# OMSI_TABLE_R12_v1.net
KiCad netlist of a schematic drawn in EAGLE
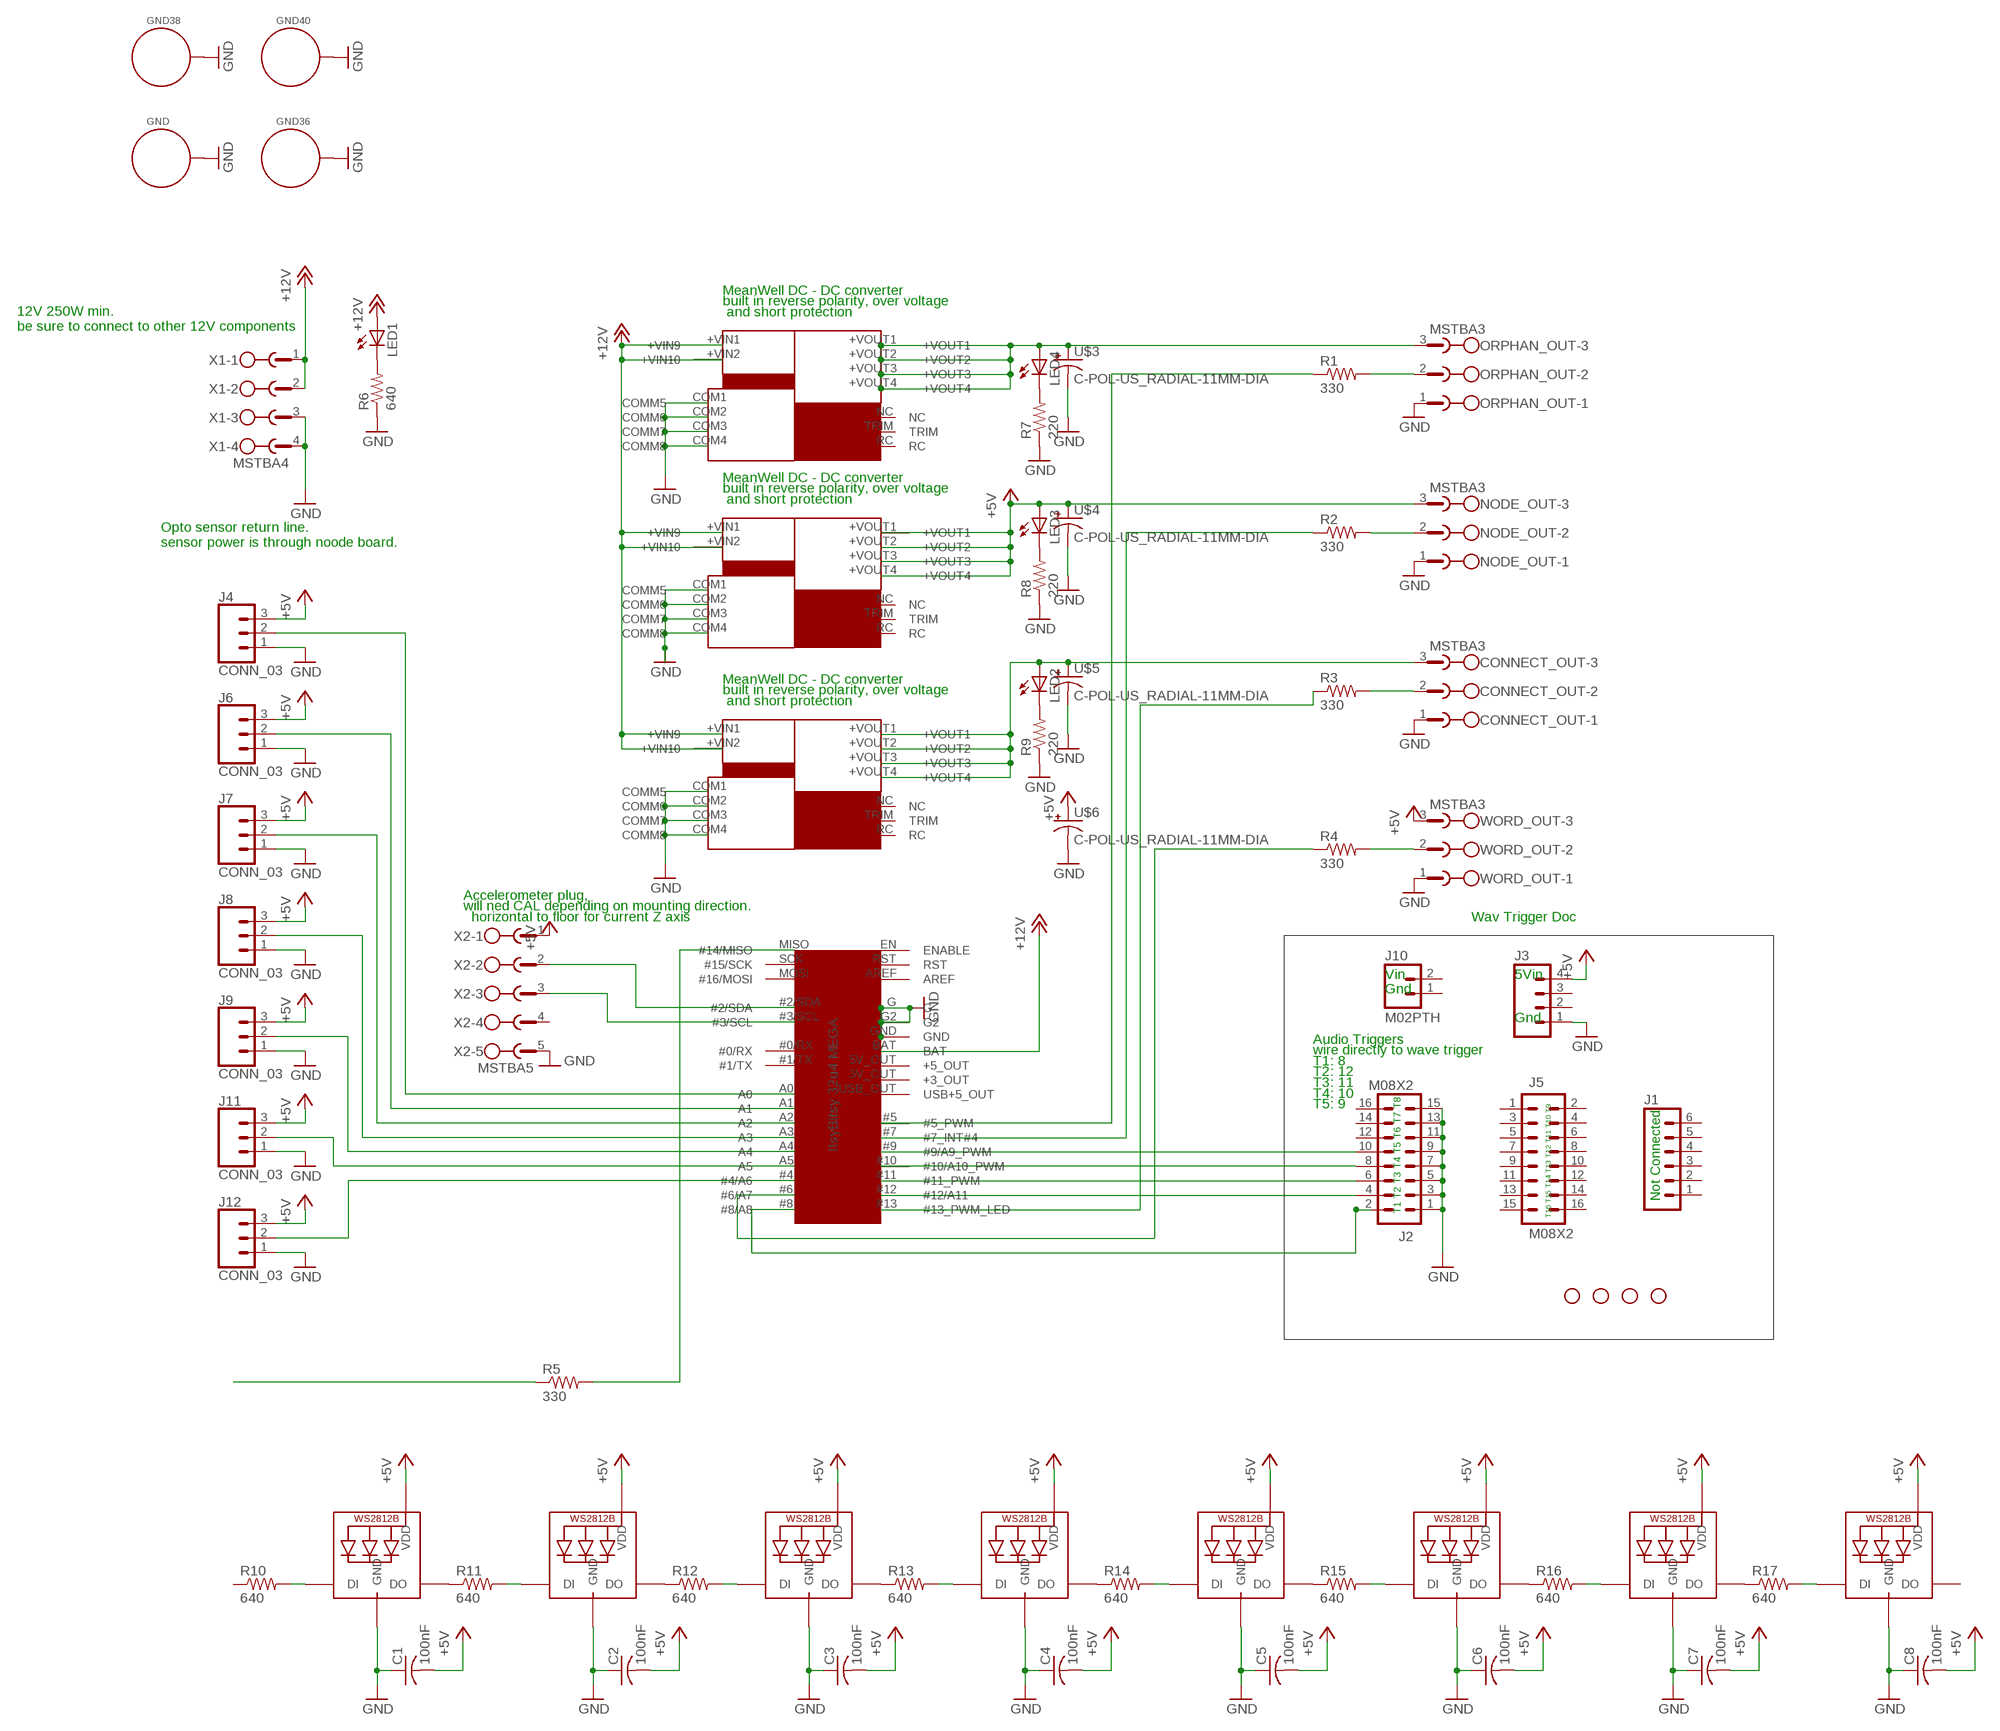
[diagram p0: schematic, sheet 1]

(export (version "E")
  (design (tool "Eeschema 10.0.6"))
  (components
    (comp (ref "C1")
      (value "100nF")
      (footprint "eagle-import:C0805")
      (libsource (lib "eagle-import") (part "C-USC0805"))
    )
    (comp (ref "C2")
      (value "100nF")
      (footprint "eagle-import:C0805")
      (libsource (lib "eagle-import") (part "C-USC0805"))
    )
    (comp (ref "C3")
      (value "100nF")
      (footprint "eagle-import:C0805")
      (libsource (lib "eagle-import") (part "C-USC0805"))
    )
    (comp (ref "C4")
      (value "100nF")
      (footprint "eagle-import:C0805")
      (libsource (lib "eagle-import") (part "C-USC0805"))
    )
    (comp (ref "C5")
      (value "100nF")
      (footprint "eagle-import:C0805")
      (libsource (lib "eagle-import") (part "C-USC0805"))
    )
    (comp (ref "C6")
      (value "100nF")
      (footprint "eagle-import:C0805")
      (libsource (lib "eagle-import") (part "C-USC0805"))
    )
    (comp (ref "C7")
      (value "100nF")
      (footprint "eagle-import:C0805")
      (libsource (lib "eagle-import") (part "C-USC0805"))
    )
    (comp (ref "C8")
      (value "100nF")
      (footprint "eagle-import:C0805")
      (libsource (lib "eagle-import") (part "C-USC0805"))
    )
    (comp (ref "CONNECT_OUT")
      (value "MSTBA3")
      (footprint "eagle-import:MSTBA3")
      (fields (field (name "MF") "FARNELL") (field (name "MPN") "1757255"))
      (libsource (lib "eagle-import") (part "MSTBA3"))
    )
    (comp (ref "GND")
      (value "STANDOFF_ELECTRICAL5-32")
      (footprint "eagle-import:STANDOFF_ELECTRICAL_5_32")
      (libsource (lib "eagle-import") (part "STANDOFF_ELECTRICAL5-32"))
    )
    (comp (ref "GND36")
      (value "STANDOFF_ELECTRICAL5-32")
      (footprint "eagle-import:STANDOFF_ELECTRICAL_5_32")
      (libsource (lib "eagle-import") (part "STANDOFF_ELECTRICAL5-32"))
    )
    (comp (ref "GND38")
      (value "STANDOFF_ELECTRICAL5-32")
      (footprint "eagle-import:STANDOFF_ELECTRICAL_5_32")
      (libsource (lib "eagle-import") (part "STANDOFF_ELECTRICAL5-32"))
    )
    (comp (ref "GND40")
      (value "STANDOFF_ELECTRICAL5-32")
      (footprint "eagle-import:STANDOFF_ELECTRICAL_5_32")
      (libsource (lib "eagle-import") (part "STANDOFF_ELECTRICAL5-32"))
    )
    (comp (ref "J1")
      (value "M06SIP")
      (footprint "eagle-import:1X06")
      (libsource (lib "eagle-import") (part "M06SIP"))
    )
    (comp (ref "J2")
      (value "M08X2")
      (footprint "eagle-import:2X8")
      (libsource (lib "eagle-import") (part "M08X2"))
    )
    (comp (ref "J3")
      (value "M04PTH")
      (footprint "eagle-import:1X04")
      (libsource (lib "eagle-import") (part "M04PTH"))
    )
    (comp (ref "J4")
      (value "CONN_03")
      (footprint "eagle-import:1X03_3.5MM_RA")
      (libsource (lib "eagle-import") (part "CONN_03"))
    )
    (comp (ref "J5")
      (value "M08X2")
      (footprint "eagle-import:2X8")
      (libsource (lib "eagle-import") (part "M08X2"))
    )
    (comp (ref "J6")
      (value "CONN_03")
      (footprint "eagle-import:1X03_3.5MM_RA")
      (libsource (lib "eagle-import") (part "CONN_03"))
    )
    (comp (ref "J7")
      (value "CONN_03")
      (footprint "eagle-import:1X03_3.5MM_RA")
      (libsource (lib "eagle-import") (part "CONN_03"))
    )
    (comp (ref "J8")
      (value "CONN_03")
      (footprint "eagle-import:1X03_3.5MM_RA")
      (libsource (lib "eagle-import") (part "CONN_03"))
    )
    (comp (ref "J9")
      (value "CONN_03")
      (footprint "eagle-import:1X03_3.5MM_RA")
      (libsource (lib "eagle-import") (part "CONN_03"))
    )
    (comp (ref "J10")
      (value "M02PTH")
      (footprint "eagle-import:1X02")
      (libsource (lib "eagle-import") (part "M02PTH"))
    )
    (comp (ref "J11")
      (value "CONN_03")
      (footprint "eagle-import:1X03_3.5MM_RA")
      (libsource (lib "eagle-import") (part "CONN_03"))
    )
    (comp (ref "J12")
      (value "CONN_03")
      (footprint "eagle-import:1X03_3.5MM_RA")
      (libsource (lib "eagle-import") (part "CONN_03"))
    )
    (comp (ref "LED1")
      (value "LEDCHIPLED_1206")
      (footprint "eagle-import:CHIPLED_1206")
      (libsource (lib "eagle-import") (part "LEDCHIPLED_1206"))
    )
    (comp (ref "LED2")
      (value "LEDCHIPLED_1206")
      (footprint "eagle-import:CHIPLED_1206")
      (libsource (lib "eagle-import") (part "LEDCHIPLED_1206"))
    )
    (comp (ref "LED3")
      (value "LEDCHIPLED_1206")
      (footprint "eagle-import:CHIPLED_1206")
      (libsource (lib "eagle-import") (part "LEDCHIPLED_1206"))
    )
    (comp (ref "LED4")
      (value "LEDCHIPLED_1206")
      (footprint "eagle-import:CHIPLED_1206")
      (libsource (lib "eagle-import") (part "LEDCHIPLED_1206"))
    )
    (comp (ref "LED5")
      (value "WS2812B")
      (footprint "eagle-import:WS2812D-F5")
      (libsource (lib "eagle-import") (part "WS2812B"))
    )
    (comp (ref "LED6")
      (value "WS2812B")
      (footprint "eagle-import:WS2812D-F5")
      (libsource (lib "eagle-import") (part "WS2812B"))
    )
    (comp (ref "LED7")
      (value "WS2812B")
      (footprint "eagle-import:WS2812D-F5")
      (libsource (lib "eagle-import") (part "WS2812B"))
    )
    (comp (ref "LED8")
      (value "WS2812B")
      (footprint "eagle-import:WS2812D-F5")
      (libsource (lib "eagle-import") (part "WS2812B"))
    )
    (comp (ref "LED9")
      (value "WS2812B")
      (footprint "eagle-import:WS2812D-F5")
      (libsource (lib "eagle-import") (part "WS2812B"))
    )
    (comp (ref "LED10")
      (value "WS2812B")
      (footprint "eagle-import:WS2812D-F5")
      (libsource (lib "eagle-import") (part "WS2812B"))
    )
    (comp (ref "LED11")
      (value "WS2812B")
      (footprint "eagle-import:WS2812D-F5")
      (libsource (lib "eagle-import") (part "WS2812B"))
    )
    (comp (ref "LED12")
      (value "WS2812B")
      (footprint "eagle-import:WS2812D-F5")
      (libsource (lib "eagle-import") (part "WS2812B"))
    )
    (comp (ref "MEANWELL_NID100_1")
      (value "MEANWELL_NID100")
      (footprint "eagle-import:MEANWELL_NID100")
      (libsource (lib "eagle-import") (part "MEANWELL_NID100"))
    )
    (comp (ref "MEANWELL_NID100_2")
      (value "MEANWELL_NID100")
      (footprint "eagle-import:MEANWELL_NID100")
      (libsource (lib "eagle-import") (part "MEANWELL_NID100"))
    )
    (comp (ref "MEANWELL_NID100_3")
      (value "MEANWELL_NID100")
      (footprint "eagle-import:MEANWELL_NID100")
      (libsource (lib "eagle-import") (part "MEANWELL_NID100"))
    )
    (comp (ref "NODE_OUT")
      (value "MSTBA3")
      (footprint "eagle-import:MSTBA3")
      (fields (field (name "MF") "FARNELL") (field (name "MPN") "1757255"))
      (libsource (lib "eagle-import") (part "MSTBA3"))
    )
    (comp (ref "ORPHAN_OUT")
      (value "MSTBA3")
      (footprint "eagle-import:MSTBA3")
      (fields (field (name "MF") "FARNELL") (field (name "MPN") "1757255"))
      (libsource (lib "eagle-import") (part "MSTBA3"))
    )
    (comp (ref "R1")
      (value "330")
      (footprint "eagle-import:RESAD1176W63L850D250B")
      (libsource (lib "eagle-import") (part "R-USAXIAL-11.7MM-PITCH_"))
    )
    (comp (ref "R2")
      (value "330")
      (footprint "eagle-import:RESAD1176W63L850D250B")
      (libsource (lib "eagle-import") (part "R-USAXIAL-11.7MM-PITCH_"))
    )
    (comp (ref "R3")
      (value "330")
      (footprint "eagle-import:RESAD1176W63L850D250B")
      (libsource (lib "eagle-import") (part "R-USAXIAL-11.7MM-PITCH_"))
    )
    (comp (ref "R4")
      (value "330")
      (footprint "eagle-import:RESAD1176W63L850D250B")
      (libsource (lib "eagle-import") (part "R-USAXIAL-11.7MM-PITCH_"))
    )
    (comp (ref "R5")
      (value "330")
      (footprint "eagle-import:RESAD1176W63L850D250B")
      (libsource (lib "eagle-import") (part "R-USAXIAL-11.7MM-PITCH_"))
    )
    (comp (ref "R6")
      (value "640")
      (footprint "eagle-import:R0805")
      (libsource (lib "eagle-import") (part "adafruit_420_R-US_R0805"))
    )
    (comp (ref "R7")
      (value "220")
      (footprint "eagle-import:R0805")
      (libsource (lib "eagle-import") (part "R-US_R0805"))
    )
    (comp (ref "R8")
      (value "220")
      (footprint "eagle-import:R0805")
      (libsource (lib "eagle-import") (part "R-US_R0805"))
    )
    (comp (ref "R9")
      (value "220")
      (footprint "eagle-import:R0805")
      (libsource (lib "eagle-import") (part "R-US_R0805"))
    )
    (comp (ref "R10")
      (value "640")
      (footprint "eagle-import:R0805")
      (libsource (lib "eagle-import") (part "adafruit_420_R-US_R0805"))
    )
    (comp (ref "R11")
      (value "640")
      (footprint "eagle-import:R0805")
      (libsource (lib "eagle-import") (part "adafruit_420_R-US_R0805"))
    )
    (comp (ref "R12")
      (value "640")
      (footprint "eagle-import:R0805")
      (libsource (lib "eagle-import") (part "adafruit_420_R-US_R0805"))
    )
    (comp (ref "R13")
      (value "640")
      (footprint "eagle-import:R0805")
      (libsource (lib "eagle-import") (part "adafruit_420_R-US_R0805"))
    )
    (comp (ref "R14")
      (value "640")
      (footprint "eagle-import:R0805")
      (libsource (lib "eagle-import") (part "adafruit_420_R-US_R0805"))
    )
    (comp (ref "R15")
      (value "640")
      (footprint "eagle-import:R0805")
      (libsource (lib "eagle-import") (part "adafruit_420_R-US_R0805"))
    )
    (comp (ref "R16")
      (value "640")
      (footprint "eagle-import:R0805")
      (libsource (lib "eagle-import") (part "adafruit_420_R-US_R0805"))
    )
    (comp (ref "R17")
      (value "640")
      (footprint "eagle-import:R0805")
      (libsource (lib "eagle-import") (part "adafruit_420_R-US_R0805"))
    )
    (comp (ref "STANDOFF5")
      (value "STAND-OFF")
      (footprint "eagle-import:STAND-OFF")
      (libsource (lib "eagle-import") (part "STAND-OFF"))
    )
    (comp (ref "STANDOFF6")
      (value "STAND-OFF")
      (footprint "eagle-import:STAND-OFF")
      (libsource (lib "eagle-import") (part "STAND-OFF"))
    )
    (comp (ref "STANDOFF7")
      (value "STAND-OFF")
      (footprint "eagle-import:STAND-OFF")
      (libsource (lib "eagle-import") (part "STAND-OFF"))
    )
    (comp (ref "STANDOFF8")
      (value "STAND-OFF")
      (footprint "eagle-import:STAND-OFF")
      (libsource (lib "eagle-import") (part "STAND-OFF"))
    )
    (comp (ref "U$1")
      (value "ITSYBITSY_32U4")
      (footprint "eagle-import:ITSYBITSY_32U4")
      (libsource (lib "eagle-import") (part "ITSYBITSY_32U4"))
    )
    (comp (ref "U$3")
      (value "C-POL-US_RADIAL-11MM-DIA")
      (footprint "eagle-import:CAPPRD508W65D1000H1100B")
      (libsource (lib "eagle-import") (part "C-POL-USRADIAL-11MM-DIA_"))
    )
    (comp (ref "U$4")
      (value "C-POL-US_RADIAL-11MM-DIA")
      (footprint "eagle-import:CAPPRD508W65D1000H1100B")
      (libsource (lib "eagle-import") (part "C-POL-USRADIAL-11MM-DIA_"))
    )
    (comp (ref "U$5")
      (value "C-POL-US_RADIAL-11MM-DIA")
      (footprint "eagle-import:CAPPRD508W65D1000H1100B")
      (libsource (lib "eagle-import") (part "C-POL-USRADIAL-11MM-DIA_"))
    )
    (comp (ref "U$6")
      (value "C-POL-US_RADIAL-11MM-DIA")
      (footprint "eagle-import:CAPPRD508W65D1000H1100B")
      (libsource (lib "eagle-import") (part "C-POL-USRADIAL-11MM-DIA_"))
    )
    (comp (ref "WORD_OUT")
      (value "MSTBA3")
      (footprint "eagle-import:MSTBA3")
      (fields (field (name "MF") "FARNELL") (field (name "MPN") "1757255"))
      (libsource (lib "eagle-import") (part "MSTBA3"))
    )
    (comp (ref "X1")
      (value "MSTBA4")
      (footprint "eagle-import:MSTBA4")
      (fields (field (name "MF") "FARNELL") (field (name "MPN") "1757268"))
      (libsource (lib "eagle-import") (part "MSTBA4"))
    )
    (comp (ref "X2")
      (value "MSTBA5")
      (footprint "eagle-import:MSTBA5")
      (fields (field (name "MPN") "1757271"))
      (libsource (lib "eagle-import") (part "MSTBA5"))
    )
  )
  (nets
    (net (code "1") (name "+5V") (class "Default")
      (node (ref "C1") (pin "2") (pinfunction "2_2") (pintype "passive"))
      (node (ref "C2") (pin "2") (pinfunction "2_2") (pintype "passive"))
      (node (ref "C3") (pin "2") (pinfunction "2_2") (pintype "passive"))
      (node (ref "C4") (pin "2") (pinfunction "2_2") (pintype "passive"))
      (node (ref "C5") (pin "2") (pinfunction "2_2") (pintype "passive"))
      (node (ref "C6") (pin "2") (pinfunction "2_2") (pintype "passive"))
      (node (ref "C7") (pin "2") (pinfunction "2_2") (pintype "passive"))
      (node (ref "C8") (pin "2") (pinfunction "2_2") (pintype "passive"))
      (node (ref "J11") (pin "3") (pinfunction "3_3") (pintype "passive"))
      (node (ref "J12") (pin "3") (pinfunction "3_3") (pintype "passive"))
      (node (ref "J3") (pin "4") (pinfunction "4_4") (pintype "passive"))
      (node (ref "J4") (pin "3") (pinfunction "3_3") (pintype "passive"))
      (node (ref "J6") (pin "3") (pinfunction "3_3") (pintype "passive"))
      (node (ref "J7") (pin "3") (pinfunction "3_3") (pintype "passive"))
      (node (ref "J8") (pin "3") (pinfunction "3_3") (pintype "passive"))
      (node (ref "J9") (pin "3") (pinfunction "3_3") (pintype "passive"))
      (node (ref "LED10") (pin "P$2") (pinfunction "VDD_P$2") (pintype "power_in"))
      (node (ref "LED11") (pin "P$2") (pinfunction "VDD_P$2") (pintype "power_in"))
      (node (ref "LED12") (pin "P$2") (pinfunction "VDD_P$2") (pintype "power_in"))
      (node (ref "LED3") (pin "A") (pinfunction "A_A") (pintype "passive"))
      (node (ref "LED5") (pin "P$2") (pinfunction "VDD_P$2") (pintype "power_in"))
      (node (ref "LED6") (pin "P$2") (pinfunction "VDD_P$2") (pintype "power_in"))
      (node (ref "LED7") (pin "P$2") (pinfunction "VDD_P$2") (pintype "power_in"))
      (node (ref "LED8") (pin "P$2") (pinfunction "VDD_P$2") (pintype "power_in"))
      (node (ref "LED9") (pin "P$2") (pinfunction "VDD_P$2") (pintype "power_in"))
      (node (ref "MEANWELL_NID100_3") (pin "+VOUT1") (pinfunction "+VOUT1_+VOUT1") (pintype "power_in"))
      (node (ref "MEANWELL_NID100_3") (pin "+VOUT2") (pinfunction "+VOUT2_+VOUT2") (pintype "power_in"))
      (node (ref "MEANWELL_NID100_3") (pin "+VOUT3") (pinfunction "+VOUT3_+VOUT3") (pintype "power_in"))
      (node (ref "MEANWELL_NID100_3") (pin "+VOUT4") (pinfunction "+VOUT4_+VOUT4") (pintype "power_in"))
      (node (ref "NODE_OUT") (pin "3") (pinfunction "1_3") (pintype "passive"))
      (node (ref "U$4") (pin "1") (pinfunction "+_1") (pintype "passive"))
      (node (ref "U$6") (pin "1") (pinfunction "+_1") (pintype "passive"))
      (node (ref "WORD_OUT") (pin "3") (pinfunction "1_3") (pintype "passive"))
      (node (ref "X2") (pin "1") (pinfunction "1_1") (pintype "passive"))
    )
    (net (code "2") (name "+12V") (class "Default")
      (node (ref "LED1") (pin "A") (pinfunction "A_A") (pintype "passive"))
      (node (ref "MEANWELL_NID100_1") (pin "+VIN1") (pinfunction "+VIN9_+VIN1") (pintype "power_in"))
      (node (ref "MEANWELL_NID100_1") (pin "+VIN2") (pinfunction "+VIN10_+VIN2") (pintype "power_in"))
      (node (ref "MEANWELL_NID100_2") (pin "+VIN1") (pinfunction "+VIN9_+VIN1") (pintype "power_in"))
      (node (ref "MEANWELL_NID100_2") (pin "+VIN2") (pinfunction "+VIN10_+VIN2") (pintype "power_in"))
      (node (ref "MEANWELL_NID100_3") (pin "+VIN1") (pinfunction "+VIN9_+VIN1") (pintype "power_in"))
      (node (ref "MEANWELL_NID100_3") (pin "+VIN2") (pinfunction "+VIN10_+VIN2") (pintype "power_in"))
      (node (ref "U$1") (pin "BAT") (pinfunction "BAT_BAT") (pintype "power_in"))
      (node (ref "X1") (pin "1") (pinfunction "1_1") (pintype "passive"))
      (node (ref "X1") (pin "2") (pinfunction "1_2") (pintype "passive"))
    )
    (net (code "3") (name "/+3_OUT") (class "Default")
      (node (ref "U$1") (pin "3V_OUT") (pinfunction "+3_OUT_3V_OUT") (pintype "power_in"))
    )
    (net (code "4") (name "/+5_OUT") (class "Default")
      (node (ref "U$1") (pin "5V_OUT") (pinfunction "+5_OUT_5V_OUT") (pintype "power_in"))
    )
    (net (code "5") (name "/AREF") (class "Default")
      (node (ref "U$1") (pin "AREF") (pinfunction "AREF_AREF") (pintype "power_in"))
    )
    (net (code "6") (name "/RST") (class "Default")
      (node (ref "U$1") (pin "RST") (pinfunction "RST_RST") (pintype "power_in"))
    )
    (net (code "7") (name "/USB+5_OUT") (class "Default")
      (node (ref "U$1") (pin "USB_OUT") (pinfunction "USB+5_OUT_USB_OUT") (pintype "power_in"))
    )
    (net (code "8") (name "GND") (class "Default")
      (node (ref "C1") (pin "1") (pinfunction "1_1") (pintype "passive"))
      (node (ref "C2") (pin "1") (pinfunction "1_1") (pintype "passive"))
      (node (ref "C3") (pin "1") (pinfunction "1_1") (pintype "passive"))
      (node (ref "C4") (pin "1") (pinfunction "1_1") (pintype "passive"))
      (node (ref "C5") (pin "1") (pinfunction "1_1") (pintype "passive"))
      (node (ref "C6") (pin "1") (pinfunction "1_1") (pintype "passive"))
      (node (ref "C7") (pin "1") (pinfunction "1_1") (pintype "passive"))
      (node (ref "C8") (pin "1") (pinfunction "1_1") (pintype "passive"))
      (node (ref "CONNECT_OUT") (pin "1") (pinfunction "1_1") (pintype "passive"))
      (node (ref "GND") (pin "P1") (pinfunction "P$1_P1") (pintype "bidirectional"))
      (node (ref "GND36") (pin "P1") (pinfunction "P$1_P1") (pintype "bidirectional"))
      (node (ref "GND38") (pin "P1") (pinfunction "P$1_P1") (pintype "bidirectional"))
      (node (ref "GND40") (pin "P1") (pinfunction "P$1_P1") (pintype "bidirectional"))
      (node (ref "J11") (pin "1") (pinfunction "1_1") (pintype "passive"))
      (node (ref "J12") (pin "1") (pinfunction "1_1") (pintype "passive"))
      (node (ref "J2") (pin "1") (pinfunction "1_1") (pintype "passive"))
      (node (ref "J2") (pin "11") (pinfunction "11_11") (pintype "passive"))
      (node (ref "J2") (pin "13") (pinfunction "13_13") (pintype "passive"))
      (node (ref "J2") (pin "15") (pinfunction "15_15") (pintype "passive"))
      (node (ref "J2") (pin "3") (pinfunction "3_3") (pintype "passive"))
      (node (ref "J2") (pin "5") (pinfunction "5_5") (pintype "passive"))
      (node (ref "J2") (pin "7") (pinfunction "7_7") (pintype "passive"))
      (node (ref "J2") (pin "9") (pinfunction "9_9") (pintype "passive"))
      (node (ref "J3") (pin "1") (pinfunction "1_1") (pintype "passive"))
      (node (ref "J4") (pin "1") (pinfunction "1_1") (pintype "passive"))
      (node (ref "J6") (pin "1") (pinfunction "1_1") (pintype "passive"))
      (node (ref "J7") (pin "1") (pinfunction "1_1") (pintype "passive"))
      (node (ref "J8") (pin "1") (pinfunction "1_1") (pintype "passive"))
      (node (ref "J9") (pin "1") (pinfunction "1_1") (pintype "passive"))
      (node (ref "LED10") (pin "P$3") (pinfunction "GND_P$3") (pintype "power_in"))
      (node (ref "LED11") (pin "P$3") (pinfunction "GND_P$3") (pintype "power_in"))
      (node (ref "LED12") (pin "P$3") (pinfunction "GND_P$3") (pintype "power_in"))
      (node (ref "LED5") (pin "P$3") (pinfunction "GND_P$3") (pintype "power_in"))
      (node (ref "LED6") (pin "P$3") (pinfunction "GND_P$3") (pintype "power_in"))
      (node (ref "LED7") (pin "P$3") (pinfunction "GND_P$3") (pintype "power_in"))
      (node (ref "LED8") (pin "P$3") (pinfunction "GND_P$3") (pintype "power_in"))
      (node (ref "LED9") (pin "P$3") (pinfunction "GND_P$3") (pintype "power_in"))
      (node (ref "MEANWELL_NID100_1") (pin "COM1") (pinfunction "COMM5_COM1") (pintype "power_in"))
      (node (ref "MEANWELL_NID100_1") (pin "COM2") (pinfunction "COMM6_COM2") (pintype "power_in"))
      (node (ref "MEANWELL_NID100_1") (pin "COM3") (pinfunction "COMM7_COM3") (pintype "power_in"))
      (node (ref "MEANWELL_NID100_1") (pin "COM4") (pinfunction "COMM8_COM4") (pintype "power_in"))
      (node (ref "MEANWELL_NID100_2") (pin "COM1") (pinfunction "COMM5_COM1") (pintype "power_in"))
      (node (ref "MEANWELL_NID100_2") (pin "COM2") (pinfunction "COMM6_COM2") (pintype "power_in"))
      (node (ref "MEANWELL_NID100_2") (pin "COM3") (pinfunction "COMM7_COM3") (pintype "power_in"))
      (node (ref "MEANWELL_NID100_2") (pin "COM4") (pinfunction "COMM8_COM4") (pintype "power_in"))
      (node (ref "MEANWELL_NID100_3") (pin "COM1") (pinfunction "COMM5_COM1") (pintype "power_in"))
      (node (ref "MEANWELL_NID100_3") (pin "COM2") (pinfunction "COMM6_COM2") (pintype "power_in"))
      (node (ref "MEANWELL_NID100_3") (pin "COM3") (pinfunction "COMM7_COM3") (pintype "power_in"))
      (node (ref "MEANWELL_NID100_3") (pin "COM4") (pinfunction "COMM8_COM4") (pintype "power_in"))
      (node (ref "NODE_OUT") (pin "1") (pinfunction "1_1") (pintype "passive"))
      (node (ref "ORPHAN_OUT") (pin "1") (pinfunction "1_1") (pintype "passive"))
      (node (ref "R6") (pin "1") (pinfunction "1_1") (pintype "passive"))
      (node (ref "R7") (pin "1") (pinfunction "1_1") (pintype "passive"))
      (node (ref "R8") (pin "1") (pinfunction "1_1") (pintype "passive"))
      (node (ref "R9") (pin "1") (pinfunction "1_1") (pintype "passive"))
      (node (ref "U$1") (pin "G") (pinfunction "G_G") (pintype "power_in"))
      (node (ref "U$1") (pin "G2") (pinfunction "G2_G2") (pintype "power_in"))
      (node (ref "U$1") (pin "GND") (pinfunction "GND_GND") (pintype "power_in"))
      (node (ref "U$3") (pin "2") (pinfunction "-_2") (pintype "passive"))
      (node (ref "U$4") (pin "2") (pinfunction "-_2") (pintype "passive"))
      (node (ref "U$5") (pin "2") (pinfunction "-_2") (pintype "passive"))
      (node (ref "U$6") (pin "2") (pinfunction "-_2") (pintype "passive"))
      (node (ref "WORD_OUT") (pin "1") (pinfunction "1_1") (pintype "passive"))
      (node (ref "X1") (pin "3") (pinfunction "1_3") (pintype "passive"))
      (node (ref "X1") (pin "4") (pinfunction "1_4") (pintype "passive"))
      (node (ref "X2") (pin "5") (pinfunction "1_5") (pintype "passive"))
    )
    (net (code "9") (name "Net-(CONNECT_OUTB-1)") (class "Default")
      (node (ref "CONNECT_OUT") (pin "2") (pinfunction "1_2") (pintype "passive"))
      (node (ref "R3") (pin "2") (pinfunction "2_2") (pintype "passive"))
    )
    (net (code "10") (name "Net-(CONNECT_OUTC-1)") (class "Default")
      (node (ref "CONNECT_OUT") (pin "3") (pinfunction "1_3") (pintype "passive"))
      (node (ref "LED2") (pin "A") (pinfunction "A_A") (pintype "passive"))
      (node (ref "MEANWELL_NID100_1") (pin "+VOUT1") (pinfunction "+VOUT1_+VOUT1") (pintype "power_in"))
      (node (ref "MEANWELL_NID100_1") (pin "+VOUT2") (pinfunction "+VOUT2_+VOUT2") (pintype "power_in"))
      (node (ref "MEANWELL_NID100_1") (pin "+VOUT3") (pinfunction "+VOUT3_+VOUT3") (pintype "power_in"))
      (node (ref "MEANWELL_NID100_1") (pin "+VOUT4") (pinfunction "+VOUT4_+VOUT4") (pintype "power_in"))
      (node (ref "U$5") (pin "1") (pinfunction "+_1") (pintype "passive"))
    )
    (net (code "11") (name "Net-(J4-Pad2)") (class "Default")
      (node (ref "J4") (pin "2") (pinfunction "2_2") (pintype "passive"))
      (node (ref "U$1") (pin "A0") (pinfunction "A0_A0") (pintype "bidirectional"))
    )
    (net (code "12") (name "Net-(J6-Pad2)") (class "Default")
      (node (ref "J6") (pin "2") (pinfunction "2_2") (pintype "passive"))
      (node (ref "U$1") (pin "A1") (pinfunction "A1_A1") (pintype "bidirectional"))
    )
    (net (code "13") (name "Net-(J7-Pad2)") (class "Default")
      (node (ref "J7") (pin "2") (pinfunction "2_2") (pintype "passive"))
      (node (ref "U$1") (pin "A2") (pinfunction "A2_A2") (pintype "bidirectional"))
    )
    (net (code "14") (name "Net-(J8-Pad2)") (class "Default")
      (node (ref "J8") (pin "2") (pinfunction "2_2") (pintype "passive"))
      (node (ref "U$1") (pin "A3") (pinfunction "A3_A3") (pintype "bidirectional"))
    )
    (net (code "15") (name "Net-(J9-Pad2)") (class "Default")
      (node (ref "J9") (pin "2") (pinfunction "2_2") (pintype "passive"))
      (node (ref "U$1") (pin "A4") (pinfunction "A4_A4") (pintype "bidirectional"))
    )
    (net (code "16") (name "Net-(J11-Pad2)") (class "Default")
      (node (ref "J11") (pin "2") (pinfunction "2_2") (pintype "passive"))
      (node (ref "U$1") (pin "A5") (pinfunction "A5_A5") (pintype "bidirectional"))
    )
    (net (code "17") (name "Net-(LED1-PadC)") (class "Default")
      (node (ref "LED1") (pin "C") (pinfunction "C_C") (pintype "passive"))
      (node (ref "R6") (pin "2") (pinfunction "2_2") (pintype "passive"))
    )
    (net (code "18") (name "Net-(LED2-PadC)") (class "Default")
      (node (ref "LED2") (pin "C") (pinfunction "C_C") (pintype "passive"))
      (node (ref "R9") (pin "2") (pinfunction "2_2") (pintype "passive"))
    )
    (net (code "19") (name "Net-(LED3-PadC)") (class "Default")
      (node (ref "LED3") (pin "C") (pinfunction "C_C") (pintype "passive"))
      (node (ref "R8") (pin "2") (pinfunction "2_2") (pintype "passive"))
    )
    (net (code "20") (name "Net-(LED4-PadC)") (class "Default")
      (node (ref "LED4") (pin "C") (pinfunction "C_C") (pintype "passive"))
      (node (ref "R7") (pin "2") (pinfunction "2_2") (pintype "passive"))
    )
    (net (code "21") (name "Net-(LED5-DI)") (class "Default")
      (node (ref "LED5") (pin "P$4") (pinfunction "DI_P$4") (pintype "input"))
      (node (ref "R10") (pin "2") (pinfunction "2_2") (pintype "passive"))
    )
    (net (code "22") (name "Net-(LED5-DO)") (class "Default")
      (node (ref "LED5") (pin "P$1") (pinfunction "DO_P$1") (pintype "output"))
      (node (ref "R11") (pin "1") (pinfunction "1_1") (pintype "passive"))
    )
    (net (code "23") (name "Net-(LED6-DI)") (class "Default")
      (node (ref "LED6") (pin "P$4") (pinfunction "DI_P$4") (pintype "input"))
      (node (ref "R11") (pin "2") (pinfunction "2_2") (pintype "passive"))
    )
    (net (code "24") (name "Net-(LED6-DO)") (class "Default")
      (node (ref "LED6") (pin "P$1") (pinfunction "DO_P$1") (pintype "output"))
      (node (ref "R12") (pin "1") (pinfunction "1_1") (pintype "passive"))
    )
    (net (code "25") (name "Net-(LED7-DI)") (class "Default")
      (node (ref "LED7") (pin "P$4") (pinfunction "DI_P$4") (pintype "input"))
      (node (ref "R12") (pin "2") (pinfunction "2_2") (pintype "passive"))
    )
    (net (code "26") (name "Net-(LED7-DO)") (class "Default")
      (node (ref "LED7") (pin "P$1") (pinfunction "DO_P$1") (pintype "output"))
      (node (ref "R13") (pin "1") (pinfunction "1_1") (pintype "passive"))
    )
    (net (code "27") (name "Net-(LED8-DI)") (class "Default")
      (node (ref "LED8") (pin "P$4") (pinfunction "DI_P$4") (pintype "input"))
      (node (ref "R13") (pin "2") (pinfunction "2_2") (pintype "passive"))
    )
    (net (code "28") (name "Net-(LED8-DO)") (class "Default")
      (node (ref "LED8") (pin "P$1") (pinfunction "DO_P$1") (pintype "output"))
      (node (ref "R14") (pin "1") (pinfunction "1_1") (pintype "passive"))
    )
    (net (code "29") (name "Net-(LED9-DI)") (class "Default")
      (node (ref "LED9") (pin "P$4") (pinfunction "DI_P$4") (pintype "input"))
      (node (ref "R14") (pin "2") (pinfunction "2_2") (pintype "passive"))
    )
    (net (code "30") (name "Net-(LED9-DO)") (class "Default")
      (node (ref "LED9") (pin "P$1") (pinfunction "DO_P$1") (pintype "output"))
      (node (ref "R15") (pin "1") (pinfunction "1_1") (pintype "passive"))
    )
    (net (code "31") (name "Net-(LED10-DI)") (class "Default")
      (node (ref "LED10") (pin "P$4") (pinfunction "DI_P$4") (pintype "input"))
      (node (ref "R15") (pin "2") (pinfunction "2_2") (pintype "passive"))
    )
    (net (code "32") (name "Net-(LED10-DO)") (class "Default")
      (node (ref "LED10") (pin "P$1") (pinfunction "DO_P$1") (pintype "output"))
      (node (ref "R16") (pin "1") (pinfunction "1_1") (pintype "passive"))
    )
    (net (code "33") (name "Net-(LED11-DI)") (class "Default")
      (node (ref "LED11") (pin "P$4") (pinfunction "DI_P$4") (pintype "input"))
      (node (ref "R16") (pin "2") (pinfunction "2_2") (pintype "passive"))
    )
    (net (code "34") (name "Net-(LED11-DO)") (class "Default")
      (node (ref "LED11") (pin "P$1") (pinfunction "DO_P$1") (pintype "output"))
      (node (ref "R17") (pin "1") (pinfunction "1_1") (pintype "passive"))
    )
    (net (code "35") (name "Net-(LED12-DI)") (class "Default")
      (node (ref "LED12") (pin "P$4") (pinfunction "DI_P$4") (pintype "input"))
      (node (ref "R17") (pin "2") (pinfunction "2_2") (pintype "passive"))
    )
    (net (code "36") (name "Net-(NODE_OUTB-1)") (class "Default")
      (node (ref "NODE_OUT") (pin "2") (pinfunction "1_2") (pintype "passive"))
      (node (ref "R2") (pin "2") (pinfunction "2_2") (pintype "passive"))
    )
    (net (code "37") (name "Net-(ORPHAN_OUTB-1)") (class "Default")
      (node (ref "ORPHAN_OUT") (pin "2") (pinfunction "1_2") (pintype "passive"))
      (node (ref "R1") (pin "2") (pinfunction "2_2") (pintype "passive"))
    )
    (net (code "38") (name "Net-(ORPHAN_OUTC-1)") (class "Default")
      (node (ref "LED4") (pin "A") (pinfunction "A_A") (pintype "passive"))
      (node (ref "MEANWELL_NID100_2") (pin "+VOUT1") (pinfunction "+VOUT1_+VOUT1") (pintype "power_in"))
      (node (ref "MEANWELL_NID100_2") (pin "+VOUT2") (pinfunction "+VOUT2_+VOUT2") (pintype "power_in"))
      (node (ref "MEANWELL_NID100_2") (pin "+VOUT3") (pinfunction "+VOUT3_+VOUT3") (pintype "power_in"))
      (node (ref "MEANWELL_NID100_2") (pin "+VOUT4") (pinfunction "+VOUT4_+VOUT4") (pintype "power_in"))
      (node (ref "ORPHAN_OUT") (pin "3") (pinfunction "1_3") (pintype "passive"))
      (node (ref "U$3") (pin "1") (pinfunction "+_1") (pintype "passive"))
    )
    (net (code "39") (name "Net-(U$1-#4{slash}A6)") (class "Default")
      (node (ref "J12") (pin "2") (pinfunction "2_2") (pintype "passive"))
      (node (ref "U$1") (pin "#4") (pinfunction "#4/A6_#4") (pintype "input"))
    )
    (net (code "40") (name "Net-(U$1-#5_PWM)") (class "Default")
      (node (ref "R1") (pin "1") (pinfunction "1_1") (pintype "passive"))
      (node (ref "U$1") (pin "#5") (pinfunction "#5_PWM_#5") (pintype "bidirectional"))
    )
    (net (code "41") (name "Net-(U$1-#6{slash}A7)") (class "Default")
      (node (ref "R4") (pin "1") (pinfunction "1_1") (pintype "passive"))
      (node (ref "U$1") (pin "#6") (pinfunction "#6/A7_#6") (pintype "bidirectional"))
    )
    (net (code "42") (name "Net-(U$1-#7_INT#4)") (class "Default")
      (node (ref "R2") (pin "1") (pinfunction "1_1") (pintype "passive"))
      (node (ref "U$1") (pin "#7") (pinfunction "#7_INT#4_#7") (pintype "bidirectional"))
    )
    (net (code "43") (name "Net-(U$1-#8{slash}A8)") (class "Default")
      (node (ref "J2") (pin "2") (pinfunction "2_2") (pintype "passive"))
      (node (ref "U$1") (pin "#8") (pinfunction "#8/A8_#8") (pintype "bidirectional"))
    )
    (net (code "44") (name "Net-(U$1-#9{slash}A9_PWM)") (class "Default")
      (node (ref "J2") (pin "10") (pinfunction "10_10") (pintype "passive"))
      (node (ref "U$1") (pin "#9") (pinfunction "#9/A9_PWM_#9") (pintype "bidirectional"))
    )
    (net (code "45") (name "Net-(U$1-#10{slash}A10_PWM)") (class "Default")
      (node (ref "J2") (pin "8") (pinfunction "8_8") (pintype "passive"))
      (node (ref "U$1") (pin "#10") (pinfunction "#10/A10_PWM_#10") (pintype "bidirectional"))
    )
    (net (code "46") (name "Net-(U$1-#11_PWM)") (class "Default")
      (node (ref "J2") (pin "6") (pinfunction "6_6") (pintype "passive"))
      (node (ref "U$1") (pin "#11") (pinfunction "#11_PWM_#11") (pintype "bidirectional"))
    )
    (net (code "47") (name "Net-(U$1-#12{slash}A11)") (class "Default")
      (node (ref "J2") (pin "4") (pinfunction "4_4") (pintype "passive"))
      (node (ref "U$1") (pin "#12") (pinfunction "#12/A11_#12") (pintype "bidirectional"))
    )
    (net (code "48") (name "Net-(U$1-#13_PWM_LED)") (class "Default")
      (node (ref "R3") (pin "1") (pinfunction "1_1") (pintype "passive"))
      (node (ref "U$1") (pin "#13") (pinfunction "#13_PWM_LED_#13") (pintype "bidirectional"))
    )
    (net (code "49") (name "Net-(U$1-#14{slash}MISO)") (class "Default")
      (node (ref "R5") (pin "2") (pinfunction "2_2") (pintype "passive"))
      (node (ref "U$1") (pin "MISO") (pinfunction "#14/MISO_MISO") (pintype "bidirectional"))
    )
    (net (code "50") (name "Net-(WORD_OUTB-1)") (class "Default")
      (node (ref "R4") (pin "2") (pinfunction "2_2") (pintype "passive"))
      (node (ref "WORD_OUT") (pin "2") (pinfunction "1_2") (pintype "passive"))
    )
    (net (code "51") (name "Net-(X2B-1)") (class "Default")
      (node (ref "U$1") (pin "#2/SDA") (pinfunction "#2/SDA_#2/SDA") (pintype "bidirectional"))
      (node (ref "X2") (pin "2") (pinfunction "1_2") (pintype "passive"))
    )
    (net (code "52") (name "Net-(X2C-1)") (class "Default")
      (node (ref "U$1") (pin "#3/SCL") (pinfunction "#3/SCL_#3/SCL") (pintype "bidirectional"))
      (node (ref "X2") (pin "3") (pinfunction "1_3") (pintype "passive"))
    )
    (net (code "53") (name "unconnected-(J1-Pad1)") (class "Default")
      (node (ref "J1") (pin "1") (pinfunction "1_1") (pintype "passive"))
    )
    (net (code "54") (name "unconnected-(J1-Pad2)") (class "Default")
      (node (ref "J1") (pin "2") (pinfunction "2_2") (pintype "passive"))
    )
    (net (code "55") (name "unconnected-(J1-Pad3)") (class "Default")
      (node (ref "J1") (pin "3") (pinfunction "3_3") (pintype "passive"))
    )
    (net (code "56") (name "unconnected-(J1-Pad4)") (class "Default")
      (node (ref "J1") (pin "4") (pinfunction "4_4") (pintype "passive"))
    )
    (net (code "57") (name "unconnected-(J1-Pad5)") (class "Default")
      (node (ref "J1") (pin "5") (pinfunction "5_5") (pintype "passive"))
    )
    (net (code "58") (name "unconnected-(J1-Pad6)") (class "Default")
      (node (ref "J1") (pin "6") (pinfunction "6_6") (pintype "passive"))
    )
    (net (code "59") (name "unconnected-(J2-Pad12)") (class "Default")
      (node (ref "J2") (pin "12") (pinfunction "12_12") (pintype "passive"))
    )
    (net (code "60") (name "unconnected-(J2-Pad14)") (class "Default")
      (node (ref "J2") (pin "14") (pinfunction "14_14") (pintype "passive"))
    )
    (net (code "61") (name "unconnected-(J2-Pad16)") (class "Default")
      (node (ref "J2") (pin "16") (pinfunction "16_16") (pintype "passive"))
    )
    (net (code "62") (name "unconnected-(J3-Pad2)") (class "Default")
      (node (ref "J3") (pin "2") (pinfunction "2_2") (pintype "passive"))
    )
    (net (code "63") (name "unconnected-(J3-Pad3)") (class "Default")
      (node (ref "J3") (pin "3") (pinfunction "3_3") (pintype "passive"))
    )
    (net (code "64") (name "unconnected-(J5-Pad1)") (class "Default")
      (node (ref "J5") (pin "1") (pinfunction "1_1") (pintype "passive"))
    )
    (net (code "65") (name "unconnected-(J5-Pad2)") (class "Default")
      (node (ref "J5") (pin "2") (pinfunction "2_2") (pintype "passive"))
    )
    (net (code "66") (name "unconnected-(J5-Pad3)") (class "Default")
      (node (ref "J5") (pin "3") (pinfunction "3_3") (pintype "passive"))
    )
    (net (code "67") (name "unconnected-(J5-Pad4)") (class "Default")
      (node (ref "J5") (pin "4") (pinfunction "4_4") (pintype "passive"))
    )
    (net (code "68") (name "unconnected-(J5-Pad5)") (class "Default")
      (node (ref "J5") (pin "5") (pinfunction "5_5") (pintype "passive"))
    )
    (net (code "69") (name "unconnected-(J5-Pad6)") (class "Default")
      (node (ref "J5") (pin "6") (pinfunction "6_6") (pintype "passive"))
    )
    (net (code "70") (name "unconnected-(J5-Pad7)") (class "Default")
      (node (ref "J5") (pin "7") (pinfunction "7_7") (pintype "passive"))
    )
    (net (code "71") (name "unconnected-(J5-Pad8)") (class "Default")
      (node (ref "J5") (pin "8") (pinfunction "8_8") (pintype "passive"))
    )
    (net (code "72") (name "unconnected-(J5-Pad9)") (class "Default")
      (node (ref "J5") (pin "9") (pinfunction "9_9") (pintype "passive"))
    )
    (net (code "73") (name "unconnected-(J5-Pad10)") (class "Default")
      (node (ref "J5") (pin "10") (pinfunction "10_10") (pintype "passive"))
    )
    (net (code "74") (name "unconnected-(J5-Pad11)") (class "Default")
      (node (ref "J5") (pin "11") (pinfunction "11_11") (pintype "passive"))
    )
    (net (code "75") (name "unconnected-(J5-Pad12)") (class "Default")
      (node (ref "J5") (pin "12") (pinfunction "12_12") (pintype "passive"))
    )
    (net (code "76") (name "unconnected-(J5-Pad13)") (class "Default")
      (node (ref "J5") (pin "13") (pinfunction "13_13") (pintype "passive"))
    )
    (net (code "77") (name "unconnected-(J5-Pad14)") (class "Default")
      (node (ref "J5") (pin "14") (pinfunction "14_14") (pintype "passive"))
    )
    (net (code "78") (name "unconnected-(J5-Pad15)") (class "Default")
      (node (ref "J5") (pin "15") (pinfunction "15_15") (pintype "passive"))
    )
    (net (code "79") (name "unconnected-(J5-Pad16)") (class "Default")
      (node (ref "J5") (pin "16") (pinfunction "16_16") (pintype "passive"))
    )
    (net (code "80") (name "unconnected-(J10-Pad1)") (class "Default")
      (node (ref "J10") (pin "1") (pinfunction "1_1") (pintype "passive"))
    )
    (net (code "81") (name "unconnected-(J10-Pad2)") (class "Default")
      (node (ref "J10") (pin "2") (pinfunction "2_2") (pintype "passive"))
    )
    (net (code "82") (name "unconnected-(LED12-DO-PadP$1)") (class "Default")
      (node (ref "LED12") (pin "P$1") (pinfunction "DO_P$1") (pintype "output"))
    )
    (net (code "83") (name "unconnected-(MEANWELL_NID100_1-PadNC)") (class "Default")
      (node (ref "MEANWELL_NID100_1") (pin "NC") (pinfunction "NC_NC") (pintype "no_connect"))
    )
    (net (code "84") (name "unconnected-(MEANWELL_NID100_1-PadRC)") (class "Default")
      (node (ref "MEANWELL_NID100_1") (pin "RC") (pinfunction "RC_RC") (pintype "no_connect"))
    )
    (net (code "85") (name "unconnected-(MEANWELL_NID100_1-PadTRIM)") (class "Default")
      (node (ref "MEANWELL_NID100_1") (pin "TRIM") (pinfunction "TRIM_TRIM") (pintype "no_connect"))
    )
    (net (code "86") (name "unconnected-(MEANWELL_NID100_2-PadNC)") (class "Default")
      (node (ref "MEANWELL_NID100_2") (pin "NC") (pinfunction "NC_NC") (pintype "no_connect"))
    )
    (net (code "87") (name "unconnected-(MEANWELL_NID100_2-PadRC)") (class "Default")
      (node (ref "MEANWELL_NID100_2") (pin "RC") (pinfunction "RC_RC") (pintype "no_connect"))
    )
    (net (code "88") (name "unconnected-(MEANWELL_NID100_2-PadTRIM)") (class "Default")
      (node (ref "MEANWELL_NID100_2") (pin "TRIM") (pinfunction "TRIM_TRIM") (pintype "no_connect"))
    )
    (net (code "89") (name "unconnected-(MEANWELL_NID100_3-PadNC)") (class "Default")
      (node (ref "MEANWELL_NID100_3") (pin "NC") (pinfunction "NC_NC") (pintype "no_connect"))
    )
    (net (code "90") (name "unconnected-(MEANWELL_NID100_3-PadRC)") (class "Default")
      (node (ref "MEANWELL_NID100_3") (pin "RC") (pinfunction "RC_RC") (pintype "no_connect"))
    )
    (net (code "91") (name "unconnected-(MEANWELL_NID100_3-PadTRIM)") (class "Default")
      (node (ref "MEANWELL_NID100_3") (pin "TRIM") (pinfunction "TRIM_TRIM") (pintype "no_connect"))
    )
    (net (code "92") (name "unconnected-(R5-Pad1)") (class "Default")
      (node (ref "R5") (pin "1") (pinfunction "1_1") (pintype "passive"))
    )
    (net (code "93") (name "unconnected-(R10-Pad1)") (class "Default")
      (node (ref "R10") (pin "1") (pinfunction "1_1") (pintype "passive"))
    )
    (net (code "94") (name "unconnected-(U$1-#15{slash}SCK-PadSCK)") (class "Default")
      (node (ref "U$1") (pin "SCK") (pinfunction "#15/SCK_SCK") (pintype "bidirectional"))
    )
    (net (code "95") (name "unconnected-(U$1-#16{slash}MOSI-PadMOSI)") (class "Default")
      (node (ref "U$1") (pin "MOSI") (pinfunction "#16/MOSI_MOSI") (pintype "bidirectional"))
    )
    (net (code "96") (name "unconnected-(U$1-ENABLE-PadEN)") (class "Default")
      (node (ref "U$1") (pin "EN") (pinfunction "ENABLE_EN") (pintype "input"))
    )
    (net (code "97") (name "unconnected-(U$1-Pad#0{slash}RX)") (class "Default")
      (node (ref "U$1") (pin "#0/RX") (pinfunction "#0/RX_#0/RX") (pintype "bidirectional"))
    )
    (net (code "98") (name "unconnected-(U$1-Pad#1{slash}TX)") (class "Default")
      (node (ref "U$1") (pin "#1/TX") (pinfunction "#1/TX_#1/TX") (pintype "bidirectional"))
    )
    (net (code "99") (name "unconnected-(X2D-1-Pad4)") (class "Default")
      (node (ref "X2") (pin "4") (pinfunction "1_4") (pintype "passive"))
    )
  )
)
